# 11_ES7201_LOOPBACK.net
KiCad netlist of a schematic drawn in Altium Designer
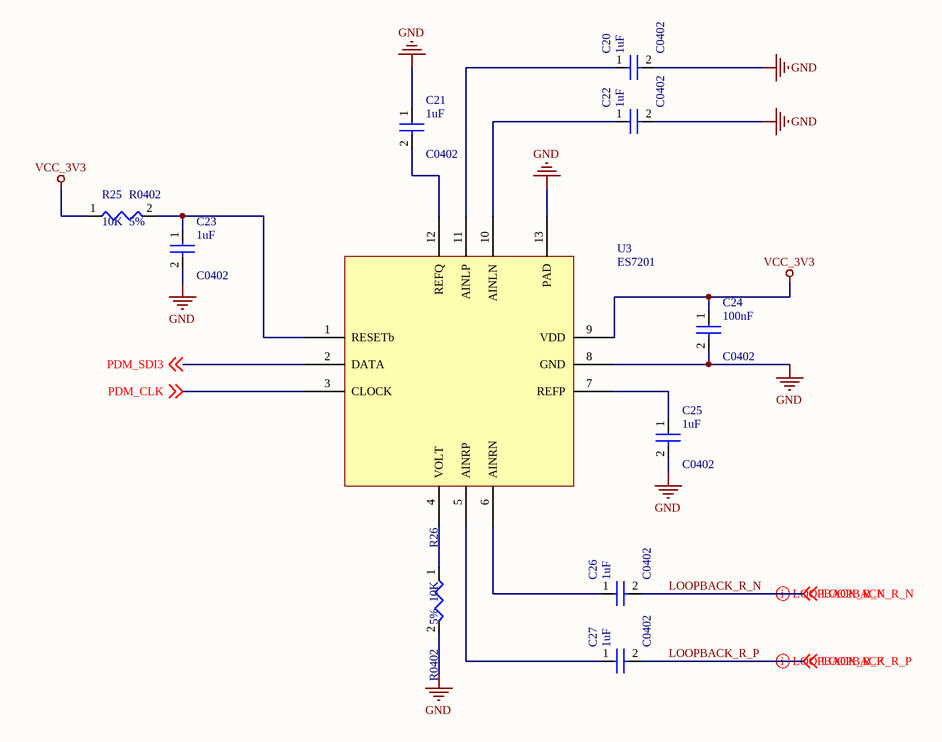
[diagram p0: 11_ES7201_LOOPBACK.SchDoc]

(export (version "E")
  (design (tool "Eeschema 10.0.6"))
  (components
    (comp (ref "C20")
      (value "1uF")
      (footprint "C0402_L")
      (description "cap,1.00uF,+/-10%,6.3V,X5R,C0402")
      (fields (field (name "PCB FOOTPRINT") "C0402"))
      (libsource (lib "*") (part "CAP NP_Dup1"))
    )
    (comp (ref "C21")
      (value "1uF")
      (footprint "C0402_L")
      (description "cap,1.00uF,+/-10%,6.3V,X5R,C0402")
      (fields (field (name "PCB FOOTPRINT") "C0402"))
      (libsource (lib "*") (part "CAP NP_Dup1"))
    )
    (comp (ref "C22")
      (value "1uF")
      (footprint "C0402_L")
      (description "cap,1.00uF,+/-10%,6.3V,X5R,C0402")
      (fields (field (name "PCB FOOTPRINT") "C0402"))
      (libsource (lib "*") (part "CAP NP_Dup1"))
    )
    (comp (ref "C23")
      (value "1uF")
      (footprint "C0402_L")
      (description "cap,1.00uF,+/-10%,6.3V,X5R,C0402")
      (fields (field (name "PCB FOOTPRINT") "C0402"))
      (libsource (lib "*") (part "CAP NP_Dup1"))
    )
    (comp (ref "C24")
      (value "100nF")
      (footprint "C0402_L")
      (description "cap,100.00nF,+/-10%,10V,X5R,C0402")
      (fields (field (name "PCB FOOTPRINT") "C0402"))
      (libsource (lib "*") (part "CAP NP_Dup1"))
    )
    (comp (ref "C25")
      (value "1uF")
      (footprint "C0402_L")
      (description "cap,1.00uF,+/-10%,6.3V,X5R,C0402")
      (fields (field (name "PCB FOOTPRINT") "C0402"))
      (libsource (lib "*") (part "CAP NP_Dup1"))
    )
    (comp (ref "C26")
      (value "1uF")
      (footprint "C0402_L")
      (description "cap,1.00uF,+/-10%,6.3V,X5R,C0402")
      (fields (field (name "PCB FOOTPRINT") "C0402"))
      (libsource (lib "*") (part "CAP NP_Dup1"))
    )
    (comp (ref "C27")
      (value "1uF")
      (footprint "C0402_L")
      (description "cap,1.00uF,+/-10%,6.3V,X5R,C0402")
      (fields (field (name "PCB FOOTPRINT") "C0402"))
      (libsource (lib "*") (part "CAP NP_Dup1"))
    )
    (comp (ref "R25")
      (value "10K")
      (footprint "R0402")
      (description "通用厚膜电阻,10K,+/-5%,R0402")
      (fields (field (name "PCB FOOTPRINT") "R0402") (field (name "TOLERANCE") "5%"))
      (libsource (lib "*") (part "RESISTOR"))
    )
    (comp (ref "R26")
      (value "10K")
      (footprint "R0402")
      (description "通用厚膜电阻,10K,+/-5%,R0402")
      (fields (field (name "PCB FOOTPRINT") "R0402") (field (name "TOLERANCE") "5%"))
      (libsource (lib "*") (part "RESISTOR"))
    )
    (comp (ref "U3")
      (value "ES7201")
      (footprint "QFN12")
      (description "ES7201 PCM to PDM Convertor")
      (libsource (lib "RV1126_RV1109_USB_AI_CAMERA_DEMO_DDR3P216DD4_V15_202100207_Library") (part "ES7201"))
    )
  )
  (nets
    (net (code "1") (name "GND") (class "Default")
      (node (ref "C20") (pin "2") (pinfunction "2_2") (pintype "passive"))
      (node (ref "C21") (pin "1") (pinfunction "1_1") (pintype "passive"))
      (node (ref "C22") (pin "2") (pinfunction "2_2") (pintype "passive"))
      (node (ref "C23") (pin "2") (pinfunction "2_2") (pintype "passive"))
      (node (ref "C24") (pin "2") (pinfunction "2_2") (pintype "passive"))
      (node (ref "C25") (pin "2") (pinfunction "2_2") (pintype "passive"))
      (node (ref "R26") (pin "2") (pinfunction "2_2") (pintype "passive"))
      (node (ref "U3") (pin "13") (pinfunction "PAD_13") (pintype "passive"))
      (node (ref "U3") (pin "8") (pinfunction "GND_8") (pintype "passive"))
    )
    (net (code "2") (name "LOOPBACK_R_N") (class "Default")
      (node (ref "C26") (pin "2") (pinfunction "2_2") (pintype "passive"))
    )
    (net (code "3") (name "LOOPBACK_R_P") (class "Default")
      (node (ref "C27") (pin "2") (pinfunction "2_2") (pintype "passive"))
    )
    (net (code "4") (name "Net-(U3-AINLN)") (class "Default")
      (node (ref "C22") (pin "1") (pinfunction "1_1") (pintype "passive"))
      (node (ref "U3") (pin "10") (pinfunction "AINLN_10") (pintype "passive"))
    )
    (net (code "5") (name "Net-(U3-AINLP)") (class "Default")
      (node (ref "C20") (pin "1") (pinfunction "1_1") (pintype "passive"))
      (node (ref "U3") (pin "11") (pinfunction "AINLP_11") (pintype "passive"))
    )
    (net (code "6") (name "Net-(U3-AINRN)") (class "Default")
      (node (ref "C26") (pin "1") (pinfunction "1_1") (pintype "passive"))
      (node (ref "U3") (pin "6") (pinfunction "AINRN_6") (pintype "passive"))
    )
    (net (code "7") (name "Net-(U3-AINRP)") (class "Default")
      (node (ref "C27") (pin "1") (pinfunction "1_1") (pintype "passive"))
      (node (ref "U3") (pin "5") (pinfunction "AINRP_5") (pintype "passive"))
    )
    (net (code "8") (name "Net-(U3-REFP)") (class "Default")
      (node (ref "C25") (pin "1") (pinfunction "1_1") (pintype "passive"))
      (node (ref "U3") (pin "7") (pinfunction "REFP_7") (pintype "passive"))
    )
    (net (code "9") (name "Net-(U3-REFQ)") (class "Default")
      (node (ref "C21") (pin "2") (pinfunction "2_2") (pintype "passive"))
      (node (ref "U3") (pin "12") (pinfunction "REFQ_12") (pintype "passive"))
    )
    (net (code "10") (name "Net-(U3-RESETb)") (class "Default")
      (node (ref "C23") (pin "1") (pinfunction "1_1") (pintype "passive"))
      (node (ref "R25") (pin "2") (pinfunction "2_2") (pintype "passive"))
      (node (ref "U3") (pin "1") (pinfunction "RESETb_1") (pintype "passive"))
    )
    (net (code "11") (name "Net-(U3-VOLT)") (class "Default")
      (node (ref "R26") (pin "1") (pinfunction "1_1") (pintype "passive"))
      (node (ref "U3") (pin "4") (pinfunction "VOLT_4") (pintype "passive"))
    )
    (net (code "12") (name "PDM_CLK") (class "Default")
      (node (ref "U3") (pin "3") (pinfunction "CLOCK_3") (pintype "passive"))
    )
    (net (code "13") (name "PDM_SDI3") (class "Default")
      (node (ref "U3") (pin "2") (pinfunction "DATA_2") (pintype "passive"))
    )
    (net (code "14") (name "VCC_3V3") (class "Default")
      (node (ref "C24") (pin "1") (pinfunction "1_1") (pintype "passive"))
      (node (ref "R25") (pin "1") (pinfunction "1_1") (pintype "passive"))
      (node (ref "U3") (pin "9") (pinfunction "VDD_9") (pintype "passive"))
    )
  )
)
